# KEY_RAW_SCH.net
KiCad netlist of a schematic drawn in Altium Designer
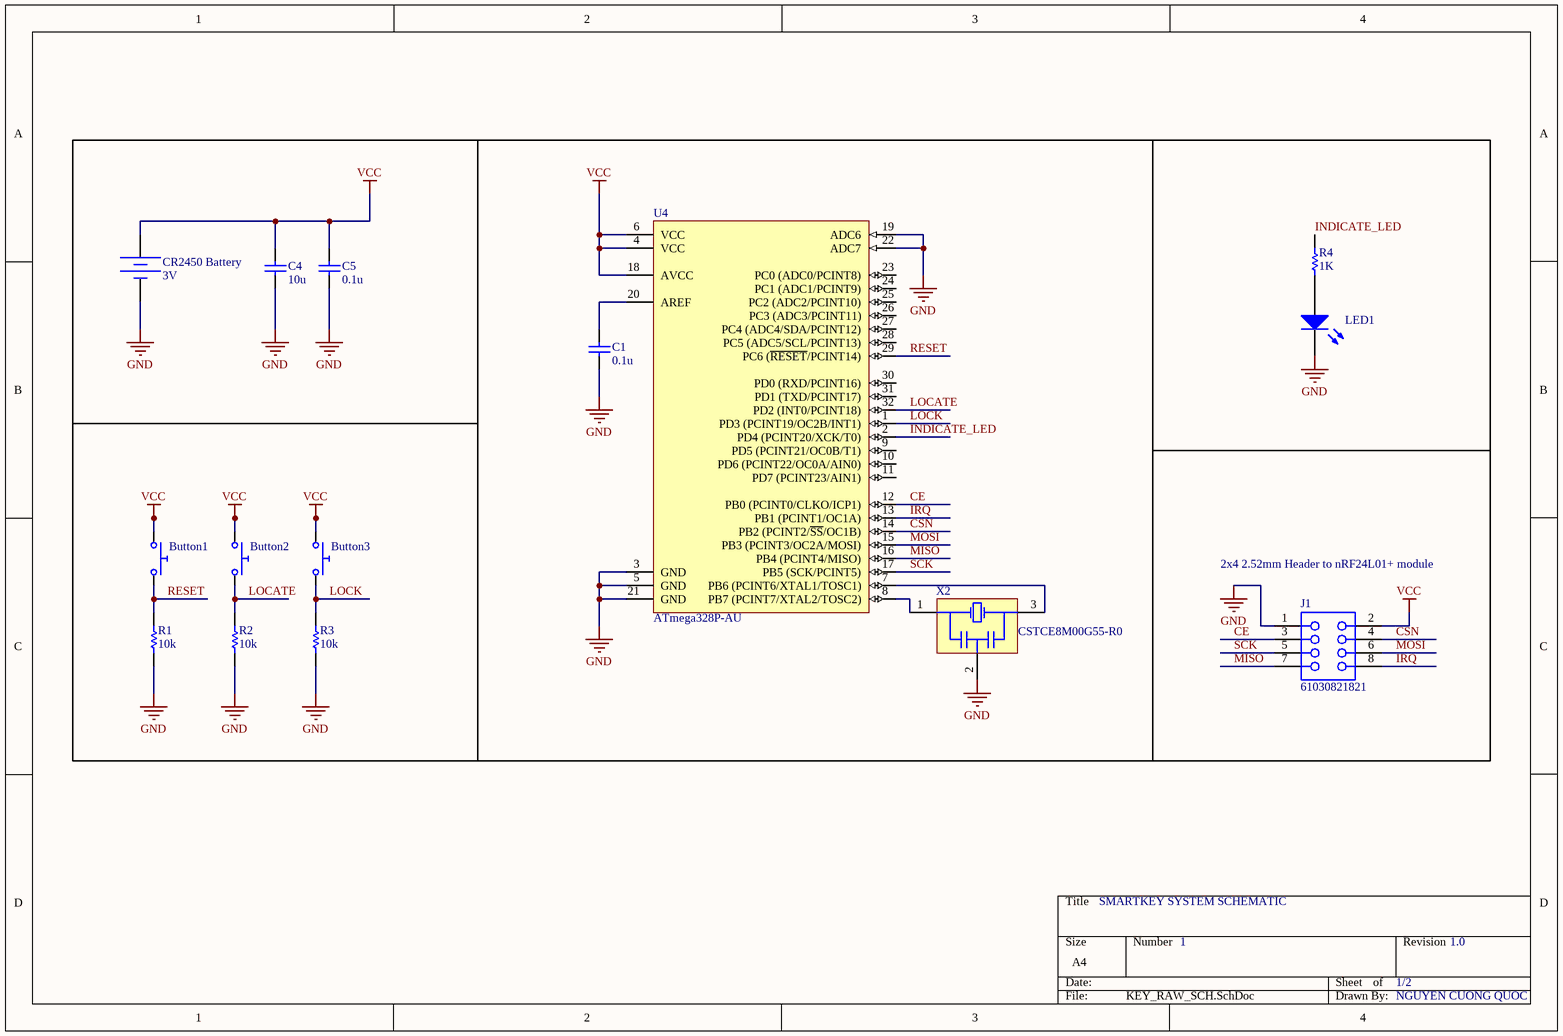
[diagram p0: KEY_RAW_SCH.SchDoc]

(export (version "E")
  (design (tool "Eeschema 10.0.6"))
  (components
    (comp (ref "Button1")
      (value "Push Button Normally Opened")
      (libsource (lib "Simulation Generic Components") (part "Push Button NO"))
    )
    (comp (ref "Button2")
      (value "Push Button Normally Opened")
      (libsource (lib "Simulation Generic Components") (part "Push Button NO"))
    )
    (comp (ref "Button3")
      (value "Push Button Normally Opened")
      (libsource (lib "Simulation Generic Components") (part "Push Button NO"))
    )
    (comp (ref "C1")
      (value "0.1u")
      (description "Capacitor")
      (libsource (lib "Simulation Generic Components") (part "Capacitor"))
    )
    (comp (ref "C4")
      (value "10u")
      (description "Capacitor")
      (libsource (lib "Simulation Generic Components") (part "Capacitor"))
    )
    (comp (ref "C5")
      (value "0.1u")
      (description "Capacitor")
      (libsource (lib "Simulation Generic Components") (part "Capacitor"))
    )
    (comp (ref "CR2450 Battery")
      (value "Constant Voltage Source")
      (fields (field (name "DC MAGNITUDE") "3V"))
      (libsource (lib "Simulation Generic Components") (part "Battery"))
    )
    (comp (ref "J1")
      (value "61030821821")
      (footprint "61030821821")
      (libsource (lib "Altium Content Vault") (part "Header_Female_2R_08P"))
    )
    (comp (ref "LED1")
      (value "Light-Emitting Diode")
      (libsource (lib "Simulation Generic Components") (part "LED"))
    )
    (comp (ref "R1")
      (value "10k")
      (description "Resistor")
      (libsource (lib "Simulation Generic Components") (part "Resistor"))
    )
    (comp (ref "R2")
      (value "10k")
      (description "Resistor")
      (libsource (lib "Simulation Generic Components") (part "Resistor"))
    )
    (comp (ref "R3")
      (value "10k")
      (description "Resistor")
      (libsource (lib "Simulation Generic Components") (part "Resistor"))
    )
    (comp (ref "R4")
      (value "1K")
      (description "Resistor")
      (libsource (lib "Simulation Generic Components") (part "Resistor"))
    )
    (comp (ref "U4")
      (value "ATmega328P-AU")
      (footprint "32A_M")
      (libsource (lib "Altium Content Vault") (part "MC-8B-ATM48-SQ32"))
    )
    (comp (ref "X2")
      (value "CSTCE8M00G55-R0")
      (footprint "MURA-CSTCE_G_A-3_V")
      (description "Ceramic Resonator, 8 MHz, +/- 0.5%, -20 to 80 degC, 3-Pin SMD, RoHS, Tape and Reel")
      (fields (field (name "TOLERANCE") "0.5%") (field (name "MANUFACTURER") "Murata"))
      (libsource (lib "Altium Content Vault") (part "MURA-CSTCE_G_A-3"))
    )
  )
  (nets
    (net (code "1") (name "/CE") (class "Default")
      (node (ref "J1") (pin "3") (pinfunction "3_3") (pintype "passive"))
      (node (ref "U4") (pin "12") (pinfunction "PB0_(PCINT0/CLKO/ICP1)_12") (pintype "bidirectional"))
    )
    (net (code "2") (name "/CSN") (class "Default")
      (node (ref "J1") (pin "4") (pinfunction "4_4") (pintype "passive"))
      (node (ref "U4") (pin "14") (pinfunction "PB2_(PCINT2/~{SS}/OC1B)_14") (pintype "bidirectional"))
    )
    (net (code "3") (name "/INDICATE_LED") (class "Default")
      (node (ref "R4") (pin "2") (pinfunction "2_2") (pintype "passive"))
      (node (ref "U4") (pin "2") (pinfunction "PD4_(PCINT20/XCK/T0)_2") (pintype "bidirectional"))
    )
    (net (code "4") (name "/IRQ") (class "Default")
      (node (ref "J1") (pin "8") (pinfunction "8_8") (pintype "passive"))
      (node (ref "U4") (pin "13") (pinfunction "PB1_(PCINT1/OC1A)_13") (pintype "bidirectional"))
    )
    (net (code "5") (name "/LOCATE") (class "Default")
      (node (ref "Button2") (pin "2") (pinfunction "2_2") (pintype "passive"))
      (node (ref "R2") (pin "2") (pinfunction "2_2") (pintype "passive"))
      (node (ref "U4") (pin "32") (pinfunction "PD2_(INT0/PCINT18)_32") (pintype "bidirectional"))
    )
    (net (code "6") (name "/LOCK") (class "Default")
      (node (ref "Button3") (pin "2") (pinfunction "2_2") (pintype "passive"))
      (node (ref "R3") (pin "2") (pinfunction "2_2") (pintype "passive"))
      (node (ref "U4") (pin "1") (pinfunction "PD3_(PCINT19/OC2B/INT1)_1") (pintype "bidirectional"))
    )
    (net (code "7") (name "/MISO") (class "Default")
      (node (ref "J1") (pin "7") (pinfunction "7_7") (pintype "passive"))
      (node (ref "U4") (pin "16") (pinfunction "PB4_(PCINT4/MISO)_16") (pintype "bidirectional"))
    )
    (net (code "8") (name "/MOSI") (class "Default")
      (node (ref "J1") (pin "6") (pinfunction "6_6") (pintype "passive"))
      (node (ref "U4") (pin "15") (pinfunction "PB3_(PCINT3/OC2A/MOSI)_15") (pintype "bidirectional"))
    )
    (net (code "9") (name "/RESET") (class "Default")
      (node (ref "Button1") (pin "2") (pinfunction "2_2") (pintype "passive"))
      (node (ref "R1") (pin "2") (pinfunction "2_2") (pintype "passive"))
      (node (ref "U4") (pin "29") (pinfunction "PC6_(~{RESET}/PCINT14)_29") (pintype "bidirectional"))
    )
    (net (code "10") (name "/SCK") (class "Default")
      (node (ref "J1") (pin "5") (pinfunction "5_5") (pintype "passive"))
      (node (ref "U4") (pin "17") (pinfunction "PB5_(SCK/PCINT5)_17") (pintype "bidirectional"))
    )
    (net (code "11") (name "GND") (class "Default")
      (node (ref "C1") (pin "1") (pinfunction "1_1") (pintype "passive"))
      (node (ref "C4") (pin "1") (pinfunction "1_1") (pintype "passive"))
      (node (ref "C5") (pin "1") (pinfunction "1_1") (pintype "passive"))
      (node (ref "CR2450 Battery") (pin "2") (pinfunction "2_2") (pintype "passive"))
      (node (ref "J1") (pin "1") (pinfunction "1_1") (pintype "passive"))
      (node (ref "LED1") (pin "2") (pinfunction "K_2") (pintype "passive"))
      (node (ref "R1") (pin "1") (pinfunction "1_1") (pintype "passive"))
      (node (ref "R2") (pin "1") (pinfunction "1_1") (pintype "passive"))
      (node (ref "R3") (pin "1") (pinfunction "1_1") (pintype "passive"))
      (node (ref "U4") (pin "19") (pinfunction "ADC6_19") (pintype "input"))
      (node (ref "U4") (pin "21") (pinfunction "GND_21") (pintype "power_in"))
      (node (ref "U4") (pin "22") (pinfunction "ADC7_22") (pintype "input"))
      (node (ref "U4") (pin "3") (pinfunction "GND_3") (pintype "power_in"))
      (node (ref "U4") (pin "5") (pinfunction "GND_5") (pintype "power_in"))
      (node (ref "X2") (pin "2") (pinfunction "GND_2") (pintype "power_in"))
    )
    (net (code "12") (name "Net-(LED1-A)") (class "Default")
      (node (ref "LED1") (pin "1") (pinfunction "A_1") (pintype "passive"))
      (node (ref "R4") (pin "1") (pinfunction "1_1") (pintype "passive"))
    )
    (net (code "13") (name "Net-(U4-AREF)") (class "Default")
      (node (ref "C1") (pin "2") (pinfunction "2_2") (pintype "passive"))
      (node (ref "U4") (pin "20") (pinfunction "AREF_20") (pintype "passive"))
    )
    (net (code "14") (name "Net-(U4-PB6_(PCINT6{slash}XTAL1{slash}TOSC1))") (class "Default")
      (node (ref "U4") (pin "7") (pinfunction "PB6_(PCINT6/XTAL1/TOSC1)_7") (pintype "bidirectional"))
      (node (ref "X2") (pin "3") (pinfunction "X2_3") (pintype "passive"))
    )
    (net (code "15") (name "Net-(U4-PB7_(PCINT7{slash}XTAL2{slash}TOSC2))") (class "Default")
      (node (ref "U4") (pin "8") (pinfunction "PB7_(PCINT7/XTAL2/TOSC2)_8") (pintype "bidirectional"))
      (node (ref "X2") (pin "1") (pinfunction "X1_1") (pintype "passive"))
    )
    (net (code "16") (name "VCC") (class "Default")
      (node (ref "Button1") (pin "1") (pinfunction "1_1") (pintype "passive"))
      (node (ref "Button2") (pin "1") (pinfunction "1_1") (pintype "passive"))
      (node (ref "Button3") (pin "1") (pinfunction "1_1") (pintype "passive"))
      (node (ref "C4") (pin "2") (pinfunction "2_2") (pintype "passive"))
      (node (ref "C5") (pin "2") (pinfunction "2_2") (pintype "passive"))
      (node (ref "CR2450 Battery") (pin "1") (pinfunction "1_1") (pintype "passive"))
      (node (ref "J1") (pin "2") (pinfunction "2_2") (pintype "passive"))
      (node (ref "U4") (pin "18") (pinfunction "AVCC_18") (pintype "power_in"))
      (node (ref "U4") (pin "4") (pinfunction "VCC_4") (pintype "power_in"))
      (node (ref "U4") (pin "6") (pinfunction "VCC_6") (pintype "power_in"))
    )
    (net (code "17") (name "unconnected-(U4-PC0_(ADC0{slash}PCINT8)-Pad23)") (class "Default")
      (node (ref "U4") (pin "23") (pinfunction "PC0_(ADC0/PCINT8)_23") (pintype "bidirectional"))
    )
    (net (code "18") (name "unconnected-(U4-PC1_(ADC1{slash}PCINT9)-Pad24)") (class "Default")
      (node (ref "U4") (pin "24") (pinfunction "PC1_(ADC1/PCINT9)_24") (pintype "bidirectional"))
    )
    (net (code "19") (name "unconnected-(U4-PC2_(ADC2{slash}PCINT10)-Pad25)") (class "Default")
      (node (ref "U4") (pin "25") (pinfunction "PC2_(ADC2/PCINT10)_25") (pintype "bidirectional"))
    )
    (net (code "20") (name "unconnected-(U4-PC3_(ADC3{slash}PCINT11)-Pad26)") (class "Default")
      (node (ref "U4") (pin "26") (pinfunction "PC3_(ADC3/PCINT11)_26") (pintype "bidirectional"))
    )
    (net (code "21") (name "unconnected-(U4-PC4_(ADC4{slash}SDA{slash}PCINT12)-Pad27)") (class "Default")
      (node (ref "U4") (pin "27") (pinfunction "PC4_(ADC4/SDA/PCINT12)_27") (pintype "bidirectional"))
    )
    (net (code "22") (name "unconnected-(U4-PC5_(ADC5{slash}SCL{slash}PCINT13)-Pad28)") (class "Default")
      (node (ref "U4") (pin "28") (pinfunction "PC5_(ADC5/SCL/PCINT13)_28") (pintype "bidirectional"))
    )
    (net (code "23") (name "unconnected-(U4-PD0_(RXD{slash}PCINT16)-Pad30)") (class "Default")
      (node (ref "U4") (pin "30") (pinfunction "PD0_(RXD/PCINT16)_30") (pintype "bidirectional"))
    )
    (net (code "24") (name "unconnected-(U4-PD1_(TXD{slash}PCINT17)-Pad31)") (class "Default")
      (node (ref "U4") (pin "31") (pinfunction "PD1_(TXD/PCINT17)_31") (pintype "bidirectional"))
    )
    (net (code "25") (name "unconnected-(U4-PD5_(PCINT21{slash}OC0B{slash}T1)-Pad9)") (class "Default")
      (node (ref "U4") (pin "9") (pinfunction "PD5_(PCINT21/OC0B/T1)_9") (pintype "bidirectional"))
    )
    (net (code "26") (name "unconnected-(U4-PD6_(PCINT22{slash}OC0A{slash}AIN0)-Pad10)") (class "Default")
      (node (ref "U4") (pin "10") (pinfunction "PD6_(PCINT22/OC0A/AIN0)_10") (pintype "bidirectional"))
    )
    (net (code "27") (name "unconnected-(U4-PD7_(PCINT23{slash}AIN1)-Pad11)") (class "Default")
      (node (ref "U4") (pin "11") (pinfunction "PD7_(PCINT23/AIN1)_11") (pintype "bidirectional"))
    )
  )
)
